# minutka_tlacitka.net
KiCad netlist of a schematic drawn in EAGLE
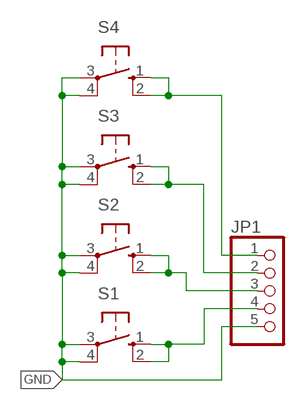
[diagram p0: schematic, sheet 1]

(export (version "E")
  (design (tool "Eeschema 10.0.6"))
  (components
    (comp (ref "JP1")
      (value "PINHD-1X5")
      (footprint "eagle-import:1X05")
      (libsource (lib "eagle-import") (part "PINHD-1X5"))
    )
    (comp (ref "S1")
      (value "40-XX")
      (footprint "eagle-import:B3F-40XX")
      (fields (field (name "MF") "OMRON COMPONENTS USA") (field (name "MPN") "B3F-4000"))
      (libsource (lib "eagle-import") (part "40-XX"))
    )
    (comp (ref "S2")
      (value "40-XX")
      (footprint "eagle-import:B3F-40XX")
      (fields (field (name "MF") "OMRON COMPONENTS USA") (field (name "MPN") "B3F-4000"))
      (libsource (lib "eagle-import") (part "40-XX"))
    )
    (comp (ref "S3")
      (value "40-XX")
      (footprint "eagle-import:B3F-40XX")
      (fields (field (name "MF") "OMRON COMPONENTS USA") (field (name "MPN") "B3F-4000"))
      (libsource (lib "eagle-import") (part "40-XX"))
    )
    (comp (ref "S4")
      (value "40-XX")
      (footprint "eagle-import:B3F-40XX")
      (fields (field (name "MF") "OMRON COMPONENTS USA") (field (name "MPN") "B3F-4000"))
      (libsource (lib "eagle-import") (part "40-XX"))
    )
  )
  (nets
    (net (code "1") (name "GND") (class "Default")
      (node (ref "JP1") (pin "5") (pinfunction "5_5") (pintype "passive"))
      (node (ref "S1") (pin "3") (pinfunction "P_3") (pintype "passive"))
      (node (ref "S1") (pin "4") (pinfunction "P1_4") (pintype "passive"))
      (node (ref "S2") (pin "3") (pinfunction "P_3") (pintype "passive"))
      (node (ref "S2") (pin "4") (pinfunction "P1_4") (pintype "passive"))
      (node (ref "S3") (pin "3") (pinfunction "P_3") (pintype "passive"))
      (node (ref "S3") (pin "4") (pinfunction "P1_4") (pintype "passive"))
      (node (ref "S4") (pin "3") (pinfunction "P_3") (pintype "passive"))
      (node (ref "S4") (pin "4") (pinfunction "P1_4") (pintype "passive"))
    )
    (net (code "2") (name "Net-(S1-S)") (class "Default")
      (node (ref "JP1") (pin "4") (pinfunction "4_4") (pintype "passive"))
      (node (ref "S1") (pin "1") (pinfunction "S_1") (pintype "passive"))
      (node (ref "S1") (pin "2") (pinfunction "S1_2") (pintype "passive"))
    )
    (net (code "3") (name "Net-(S2-S)") (class "Default")
      (node (ref "JP1") (pin "3") (pinfunction "3_3") (pintype "passive"))
      (node (ref "S2") (pin "1") (pinfunction "S_1") (pintype "passive"))
      (node (ref "S2") (pin "2") (pinfunction "S1_2") (pintype "passive"))
    )
    (net (code "4") (name "Net-(S3-S)") (class "Default")
      (node (ref "JP1") (pin "2") (pinfunction "2_2") (pintype "passive"))
      (node (ref "S3") (pin "1") (pinfunction "S_1") (pintype "passive"))
      (node (ref "S3") (pin "2") (pinfunction "S1_2") (pintype "passive"))
    )
    (net (code "5") (name "Net-(S4-S)") (class "Default")
      (node (ref "JP1") (pin "1") (pinfunction "1_1") (pintype "passive"))
      (node (ref "S4") (pin "1") (pinfunction "S_1") (pintype "passive"))
      (node (ref "S4") (pin "2") (pinfunction "S1_2") (pintype "passive"))
    )
  )
)
